# MPX_4067.net
KiCad netlist of a schematic drawn in EAGLE
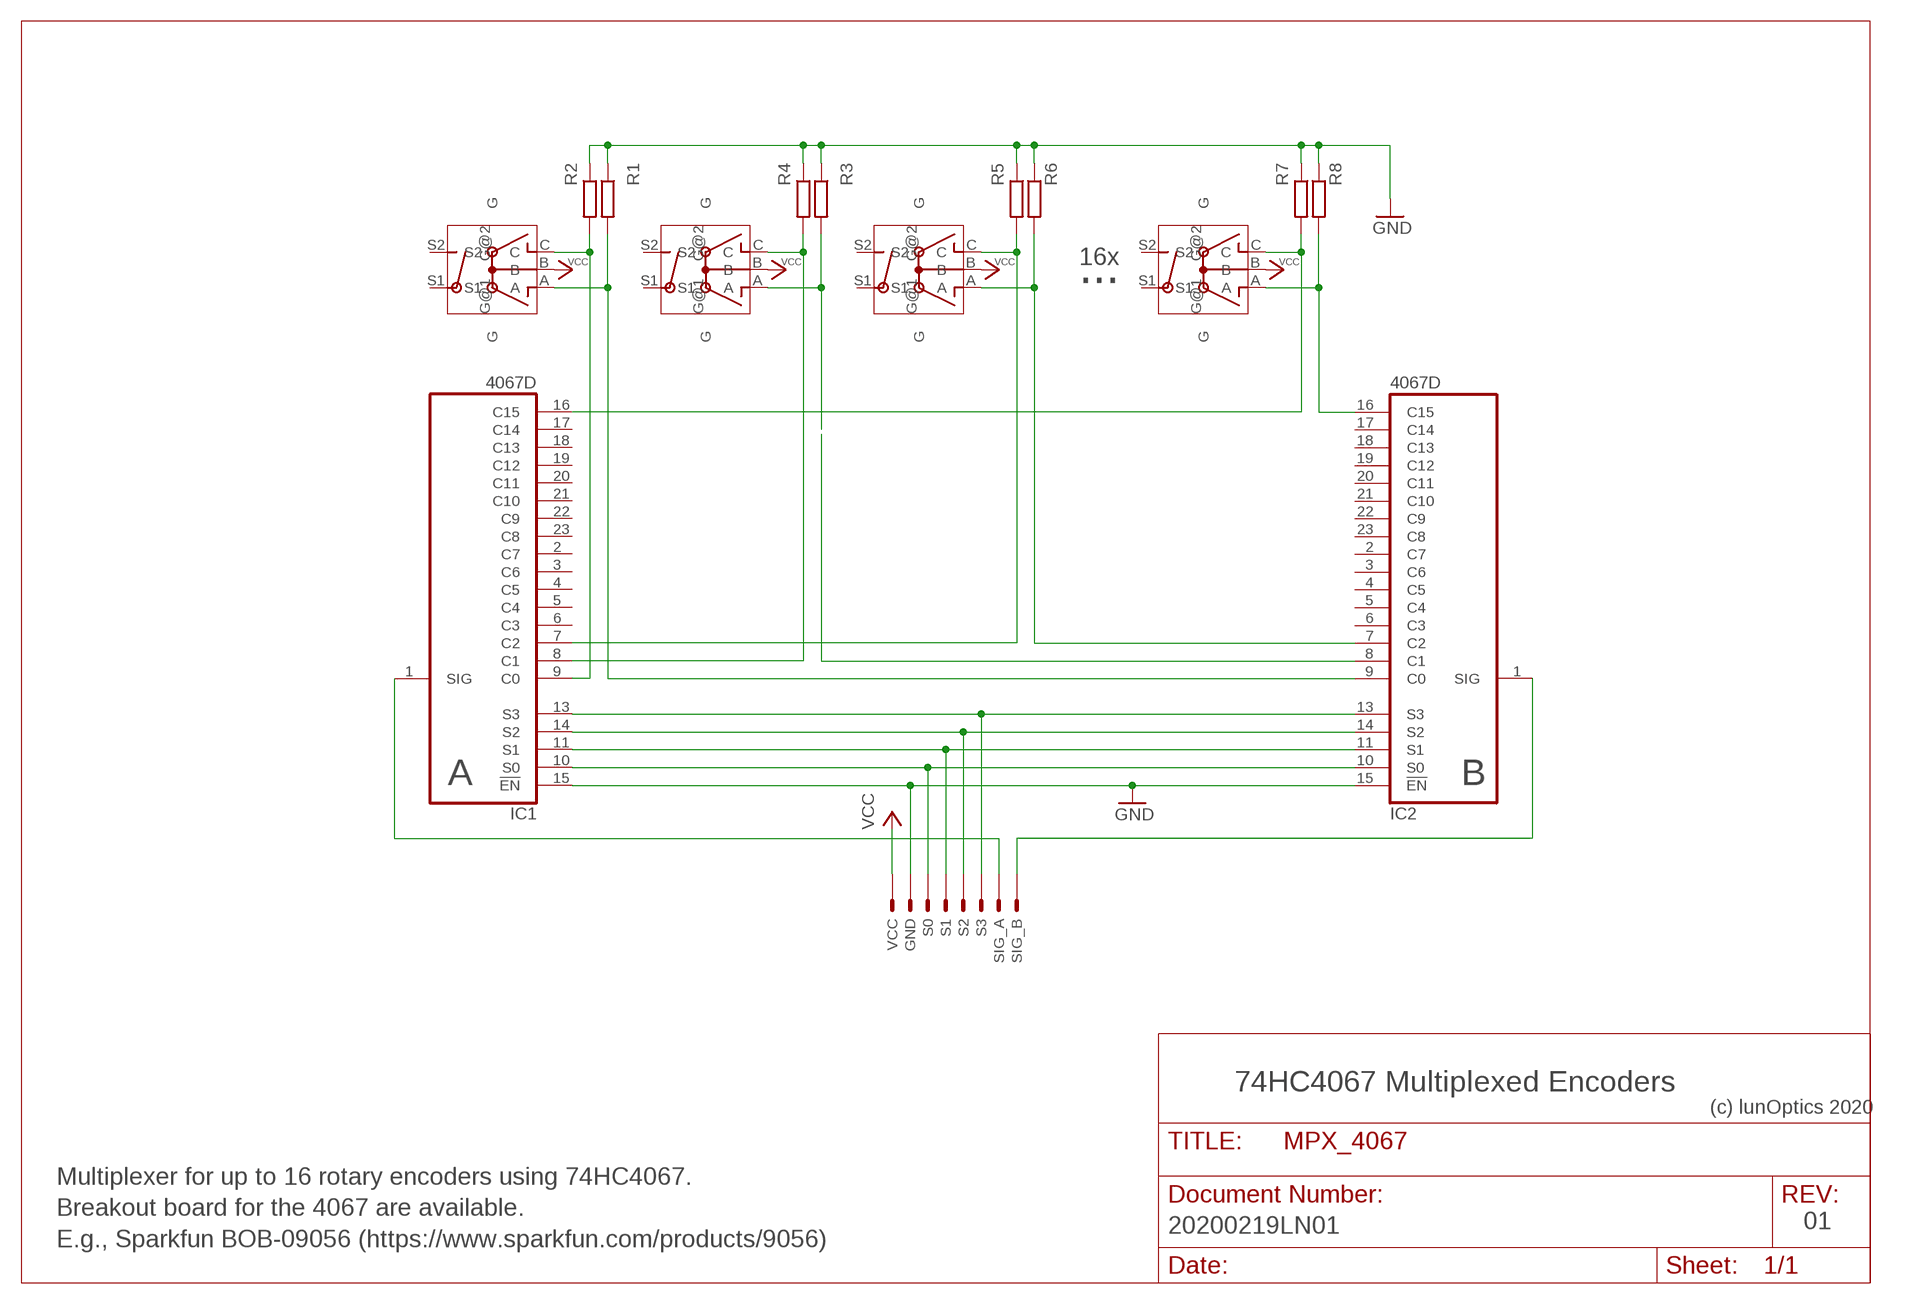
[diagram p0: schematic, sheet 1]

(export (version "E")
  (design (tool "Eeschema 10.0.6"))
  (components
    (comp (ref "EN1")
      (value "ENCODER")
      (footprint "eagle-import:ENCODER")
      (libsource (lib "eagle-import") (part "ENCODER"))
    )
    (comp (ref "EN2")
      (value "ENCODER")
      (footprint "eagle-import:ENCODER")
      (libsource (lib "eagle-import") (part "ENCODER"))
    )
    (comp (ref "EN3")
      (value "ENCODER")
      (footprint "eagle-import:ENCODER")
      (libsource (lib "eagle-import") (part "ENCODER"))
    )
    (comp (ref "EN4")
      (value "ENCODER")
      (footprint "eagle-import:ENCODER")
      (libsource (lib "eagle-import") (part "ENCODER"))
    )
    (comp (ref "IC1")
      (value "4067D")
      (footprint "eagle-import:SO24W")
      (libsource (lib "eagle-import") (part "4067D"))
    )
    (comp (ref "IC2")
      (value "4067D")
      (footprint "eagle-import:SO24W")
      (libsource (lib "eagle-import") (part "4067D"))
    )
    (comp (ref "R1")
      (value "R-EU_0204/7")
      (footprint "eagle-import:0204_7")
      (libsource (lib "eagle-import") (part "R-EU_0204/7"))
    )
    (comp (ref "R2")
      (value "R-EU_0204/7")
      (footprint "eagle-import:0204_7")
      (libsource (lib "eagle-import") (part "R-EU_0204/7"))
    )
    (comp (ref "R3")
      (value "R-EU_0204/7")
      (footprint "eagle-import:0204_7")
      (libsource (lib "eagle-import") (part "R-EU_0204/7"))
    )
    (comp (ref "R4")
      (value "R-EU_0204/7")
      (footprint "eagle-import:0204_7")
      (libsource (lib "eagle-import") (part "R-EU_0204/7"))
    )
    (comp (ref "R5")
      (value "R-EU_0204/7")
      (footprint "eagle-import:0204_7")
      (libsource (lib "eagle-import") (part "R-EU_0204/7"))
    )
    (comp (ref "R6")
      (value "R-EU_0204/7")
      (footprint "eagle-import:0204_7")
      (libsource (lib "eagle-import") (part "R-EU_0204/7"))
    )
    (comp (ref "R7")
      (value "R-EU_0204/7")
      (footprint "eagle-import:0204_7")
      (libsource (lib "eagle-import") (part "R-EU_0204/7"))
    )
    (comp (ref "R8")
      (value "R-EU_0204/7")
      (footprint "eagle-import:0204_7")
      (libsource (lib "eagle-import") (part "R-EU_0204/7"))
    )
    (comp (ref "X1")
      (value "057-010-0")
      (footprint "eagle-import:057-010-0")
      (libsource (lib "eagle-import") (part "057-010-0"))
    )
  )
  (nets
    (net (code "1") (name "GND") (class "Default")
      (node (ref "IC1") (pin "15") (pinfunction "~{EN}_15") (pintype "input"))
      (node (ref "IC2") (pin "15") (pinfunction "~{EN}_15") (pintype "input"))
      (node (ref "R1") (pin "1") (pinfunction "1_1") (pintype "passive"))
      (node (ref "R2") (pin "1") (pinfunction "1_1") (pintype "passive"))
      (node (ref "R3") (pin "1") (pinfunction "1_1") (pintype "passive"))
      (node (ref "R4") (pin "1") (pinfunction "1_1") (pintype "passive"))
      (node (ref "R5") (pin "1") (pinfunction "1_1") (pintype "passive"))
      (node (ref "R6") (pin "1") (pinfunction "1_1") (pintype "passive"))
      (node (ref "R7") (pin "1") (pinfunction "1_1") (pintype "passive"))
      (node (ref "R8") (pin "1") (pinfunction "1_1") (pintype "passive"))
      (node (ref "X1") (pin "2") (pinfunction "S_2") (pintype "passive"))
    )
    (net (code "2") (name "Net-(EN2-PadA)") (class "Default")
      (node (ref "EN2") (pin "A") (pinfunction "A_A") (pintype "passive"))
      (node (ref "R3") (pin "2") (pinfunction "2_2") (pintype "passive"))
    )
    (net (code "3") (name "Net-(IC1A-C0)") (class "Default")
      (node (ref "EN1") (pin "C") (pinfunction "C_C") (pintype "passive"))
      (node (ref "IC1") (pin "9") (pinfunction "C0_9") (pintype "input"))
      (node (ref "R2") (pin "2") (pinfunction "2_2") (pintype "passive"))
    )
    (net (code "4") (name "Net-(IC1A-C1)") (class "Default")
      (node (ref "EN2") (pin "C") (pinfunction "C_C") (pintype "passive"))
      (node (ref "IC1") (pin "8") (pinfunction "C1_8") (pintype "input"))
      (node (ref "R4") (pin "2") (pinfunction "2_2") (pintype "passive"))
    )
    (net (code "5") (name "Net-(IC1A-C2)") (class "Default")
      (node (ref "EN3") (pin "C") (pinfunction "C_C") (pintype "passive"))
      (node (ref "IC1") (pin "7") (pinfunction "C2_7") (pintype "input"))
      (node (ref "R5") (pin "2") (pinfunction "2_2") (pintype "passive"))
    )
    (net (code "6") (name "Net-(IC1A-C15)") (class "Default")
      (node (ref "EN4") (pin "C") (pinfunction "C_C") (pintype "passive"))
      (node (ref "IC1") (pin "16") (pinfunction "C15_16") (pintype "input"))
      (node (ref "R7") (pin "2") (pinfunction "2_2") (pintype "passive"))
    )
    (net (code "7") (name "Net-(IC1A-S0)") (class "Default")
      (node (ref "IC1") (pin "10") (pinfunction "S0_10") (pintype "input"))
      (node (ref "IC2") (pin "10") (pinfunction "S0_10") (pintype "input"))
      (node (ref "X1") (pin "3") (pinfunction "S_3") (pintype "passive"))
    )
    (net (code "8") (name "Net-(IC1A-S1)") (class "Default")
      (node (ref "IC1") (pin "11") (pinfunction "S1_11") (pintype "input"))
      (node (ref "IC2") (pin "11") (pinfunction "S1_11") (pintype "input"))
      (node (ref "X1") (pin "4") (pinfunction "S_4") (pintype "passive"))
    )
    (net (code "9") (name "Net-(IC1A-S2)") (class "Default")
      (node (ref "IC1") (pin "14") (pinfunction "S2_14") (pintype "input"))
      (node (ref "IC2") (pin "14") (pinfunction "S2_14") (pintype "input"))
      (node (ref "X1") (pin "5") (pinfunction "S_5") (pintype "passive"))
    )
    (net (code "10") (name "Net-(IC1A-S3)") (class "Default")
      (node (ref "IC1") (pin "13") (pinfunction "S3_13") (pintype "input"))
      (node (ref "IC2") (pin "13") (pinfunction "S3_13") (pintype "input"))
      (node (ref "X1") (pin "6") (pinfunction "S_6") (pintype "passive"))
    )
    (net (code "11") (name "Net-(IC1A-SIG)") (class "Default")
      (node (ref "IC1") (pin "1") (pinfunction "SIG_1") (pintype "output"))
      (node (ref "X1") (pin "7") (pinfunction "S_7") (pintype "passive"))
    )
    (net (code "12") (name "Net-(IC2A-C0)") (class "Default")
      (node (ref "EN1") (pin "A") (pinfunction "A_A") (pintype "passive"))
      (node (ref "IC2") (pin "9") (pinfunction "C0_9") (pintype "input"))
      (node (ref "R1") (pin "2") (pinfunction "2_2") (pintype "passive"))
    )
    (net (code "13") (name "Net-(IC2A-C2)") (class "Default")
      (node (ref "EN3") (pin "A") (pinfunction "A_A") (pintype "passive"))
      (node (ref "IC2") (pin "7") (pinfunction "C2_7") (pintype "input"))
      (node (ref "R6") (pin "2") (pinfunction "2_2") (pintype "passive"))
    )
    (net (code "14") (name "Net-(IC2A-C15)") (class "Default")
      (node (ref "EN4") (pin "A") (pinfunction "A_A") (pintype "passive"))
      (node (ref "IC2") (pin "16") (pinfunction "C15_16") (pintype "input"))
      (node (ref "R8") (pin "2") (pinfunction "2_2") (pintype "passive"))
    )
    (net (code "15") (name "Net-(IC2A-SIG)") (class "Default")
      (node (ref "IC2") (pin "1") (pinfunction "SIG_1") (pintype "output"))
      (node (ref "X1") (pin "8") (pinfunction "S_8") (pintype "passive"))
    )
    (net (code "16") (name "VCC") (class "Default")
      (node (ref "EN1") (pin "B") (pinfunction "B_B") (pintype "passive"))
      (node (ref "EN2") (pin "B") (pinfunction "B_B") (pintype "passive"))
      (node (ref "EN3") (pin "B") (pinfunction "B_B") (pintype "passive"))
      (node (ref "EN4") (pin "B") (pinfunction "B_B") (pintype "passive"))
      (node (ref "X1") (pin "1") (pinfunction "S_1") (pintype "passive"))
    )
    (net (code "17") (name "unconnected-(EN1-G-PadG@1)") (class "Default")
      (node (ref "EN1") (pin "G@1") (pinfunction "G_G@1") (pintype "passive"))
    )
    (net (code "18") (name "unconnected-(EN1-G-PadG@2)") (class "Default")
      (node (ref "EN1") (pin "G@2") (pinfunction "G_G@2") (pintype "passive"))
    )
    (net (code "19") (name "unconnected-(EN1-PadS1)") (class "Default")
      (node (ref "EN1") (pin "S1") (pinfunction "S1_S1") (pintype "passive"))
    )
    (net (code "20") (name "unconnected-(EN1-PadS2)") (class "Default")
      (node (ref "EN1") (pin "S2") (pinfunction "S2_S2") (pintype "passive"))
    )
    (net (code "21") (name "unconnected-(EN2-G-PadG@1)") (class "Default")
      (node (ref "EN2") (pin "G@1") (pinfunction "G_G@1") (pintype "passive"))
    )
    (net (code "22") (name "unconnected-(EN2-G-PadG@2)") (class "Default")
      (node (ref "EN2") (pin "G@2") (pinfunction "G_G@2") (pintype "passive"))
    )
    (net (code "23") (name "unconnected-(EN2-PadS1)") (class "Default")
      (node (ref "EN2") (pin "S1") (pinfunction "S1_S1") (pintype "passive"))
    )
    (net (code "24") (name "unconnected-(EN2-PadS2)") (class "Default")
      (node (ref "EN2") (pin "S2") (pinfunction "S2_S2") (pintype "passive"))
    )
    (net (code "25") (name "unconnected-(EN3-G-PadG@1)") (class "Default")
      (node (ref "EN3") (pin "G@1") (pinfunction "G_G@1") (pintype "passive"))
    )
    (net (code "26") (name "unconnected-(EN3-G-PadG@2)") (class "Default")
      (node (ref "EN3") (pin "G@2") (pinfunction "G_G@2") (pintype "passive"))
    )
    (net (code "27") (name "unconnected-(EN3-PadS1)") (class "Default")
      (node (ref "EN3") (pin "S1") (pinfunction "S1_S1") (pintype "passive"))
    )
    (net (code "28") (name "unconnected-(EN3-PadS2)") (class "Default")
      (node (ref "EN3") (pin "S2") (pinfunction "S2_S2") (pintype "passive"))
    )
    (net (code "29") (name "unconnected-(EN4-G-PadG@1)") (class "Default")
      (node (ref "EN4") (pin "G@1") (pinfunction "G_G@1") (pintype "passive"))
    )
    (net (code "30") (name "unconnected-(EN4-G-PadG@2)") (class "Default")
      (node (ref "EN4") (pin "G@2") (pinfunction "G_G@2") (pintype "passive"))
    )
    (net (code "31") (name "unconnected-(EN4-PadS1)") (class "Default")
      (node (ref "EN4") (pin "S1") (pinfunction "S1_S1") (pintype "passive"))
    )
    (net (code "32") (name "unconnected-(EN4-PadS2)") (class "Default")
      (node (ref "EN4") (pin "S2") (pinfunction "S2_S2") (pintype "passive"))
    )
    (net (code "33") (name "unconnected-(IC1A-C3-Pad6)") (class "Default")
      (node (ref "IC1") (pin "6") (pinfunction "C3_6") (pintype "input"))
    )
    (net (code "34") (name "unconnected-(IC1A-C4-Pad5)") (class "Default")
      (node (ref "IC1") (pin "5") (pinfunction "C4_5") (pintype "input"))
    )
    (net (code "35") (name "unconnected-(IC1A-C5-Pad4)") (class "Default")
      (node (ref "IC1") (pin "4") (pinfunction "C5_4") (pintype "input"))
    )
    (net (code "36") (name "unconnected-(IC1A-C6-Pad3)") (class "Default")
      (node (ref "IC1") (pin "3") (pinfunction "C6_3") (pintype "input"))
    )
    (net (code "37") (name "unconnected-(IC1A-C7-Pad2)") (class "Default")
      (node (ref "IC1") (pin "2") (pinfunction "C7_2") (pintype "input"))
    )
    (net (code "38") (name "unconnected-(IC1A-C8-Pad23)") (class "Default")
      (node (ref "IC1") (pin "23") (pinfunction "C8_23") (pintype "input"))
    )
    (net (code "39") (name "unconnected-(IC1A-C9-Pad22)") (class "Default")
      (node (ref "IC1") (pin "22") (pinfunction "C9_22") (pintype "input"))
    )
    (net (code "40") (name "unconnected-(IC1A-C10-Pad21)") (class "Default")
      (node (ref "IC1") (pin "21") (pinfunction "C10_21") (pintype "input"))
    )
    (net (code "41") (name "unconnected-(IC1A-C11-Pad20)") (class "Default")
      (node (ref "IC1") (pin "20") (pinfunction "C11_20") (pintype "input"))
    )
    (net (code "42") (name "unconnected-(IC1A-C12-Pad19)") (class "Default")
      (node (ref "IC1") (pin "19") (pinfunction "C12_19") (pintype "input"))
    )
    (net (code "43") (name "unconnected-(IC1A-C13-Pad18)") (class "Default")
      (node (ref "IC1") (pin "18") (pinfunction "C13_18") (pintype "input"))
    )
    (net (code "44") (name "unconnected-(IC1A-C14-Pad17)") (class "Default")
      (node (ref "IC1") (pin "17") (pinfunction "C14_17") (pintype "input"))
    )
    (net (code "45") (name "unconnected-(IC2A-C1-Pad8)") (class "Default")
      (node (ref "IC2") (pin "8") (pinfunction "C1_8") (pintype "input"))
    )
    (net (code "46") (name "unconnected-(IC2A-C3-Pad6)") (class "Default")
      (node (ref "IC2") (pin "6") (pinfunction "C3_6") (pintype "input"))
    )
    (net (code "47") (name "unconnected-(IC2A-C4-Pad5)") (class "Default")
      (node (ref "IC2") (pin "5") (pinfunction "C4_5") (pintype "input"))
    )
    (net (code "48") (name "unconnected-(IC2A-C5-Pad4)") (class "Default")
      (node (ref "IC2") (pin "4") (pinfunction "C5_4") (pintype "input"))
    )
    (net (code "49") (name "unconnected-(IC2A-C6-Pad3)") (class "Default")
      (node (ref "IC2") (pin "3") (pinfunction "C6_3") (pintype "input"))
    )
    (net (code "50") (name "unconnected-(IC2A-C7-Pad2)") (class "Default")
      (node (ref "IC2") (pin "2") (pinfunction "C7_2") (pintype "input"))
    )
    (net (code "51") (name "unconnected-(IC2A-C8-Pad23)") (class "Default")
      (node (ref "IC2") (pin "23") (pinfunction "C8_23") (pintype "input"))
    )
    (net (code "52") (name "unconnected-(IC2A-C9-Pad22)") (class "Default")
      (node (ref "IC2") (pin "22") (pinfunction "C9_22") (pintype "input"))
    )
    (net (code "53") (name "unconnected-(IC2A-C10-Pad21)") (class "Default")
      (node (ref "IC2") (pin "21") (pinfunction "C10_21") (pintype "input"))
    )
    (net (code "54") (name "unconnected-(IC2A-C11-Pad20)") (class "Default")
      (node (ref "IC2") (pin "20") (pinfunction "C11_20") (pintype "input"))
    )
    (net (code "55") (name "unconnected-(IC2A-C12-Pad19)") (class "Default")
      (node (ref "IC2") (pin "19") (pinfunction "C12_19") (pintype "input"))
    )
    (net (code "56") (name "unconnected-(IC2A-C13-Pad18)") (class "Default")
      (node (ref "IC2") (pin "18") (pinfunction "C13_18") (pintype "input"))
    )
    (net (code "57") (name "unconnected-(IC2A-C14-Pad17)") (class "Default")
      (node (ref "IC2") (pin "17") (pinfunction "C14_17") (pintype "input"))
    )
  )
)
